# Sheet1.net
KiCad netlist of a schematic drawn in Altium Designer
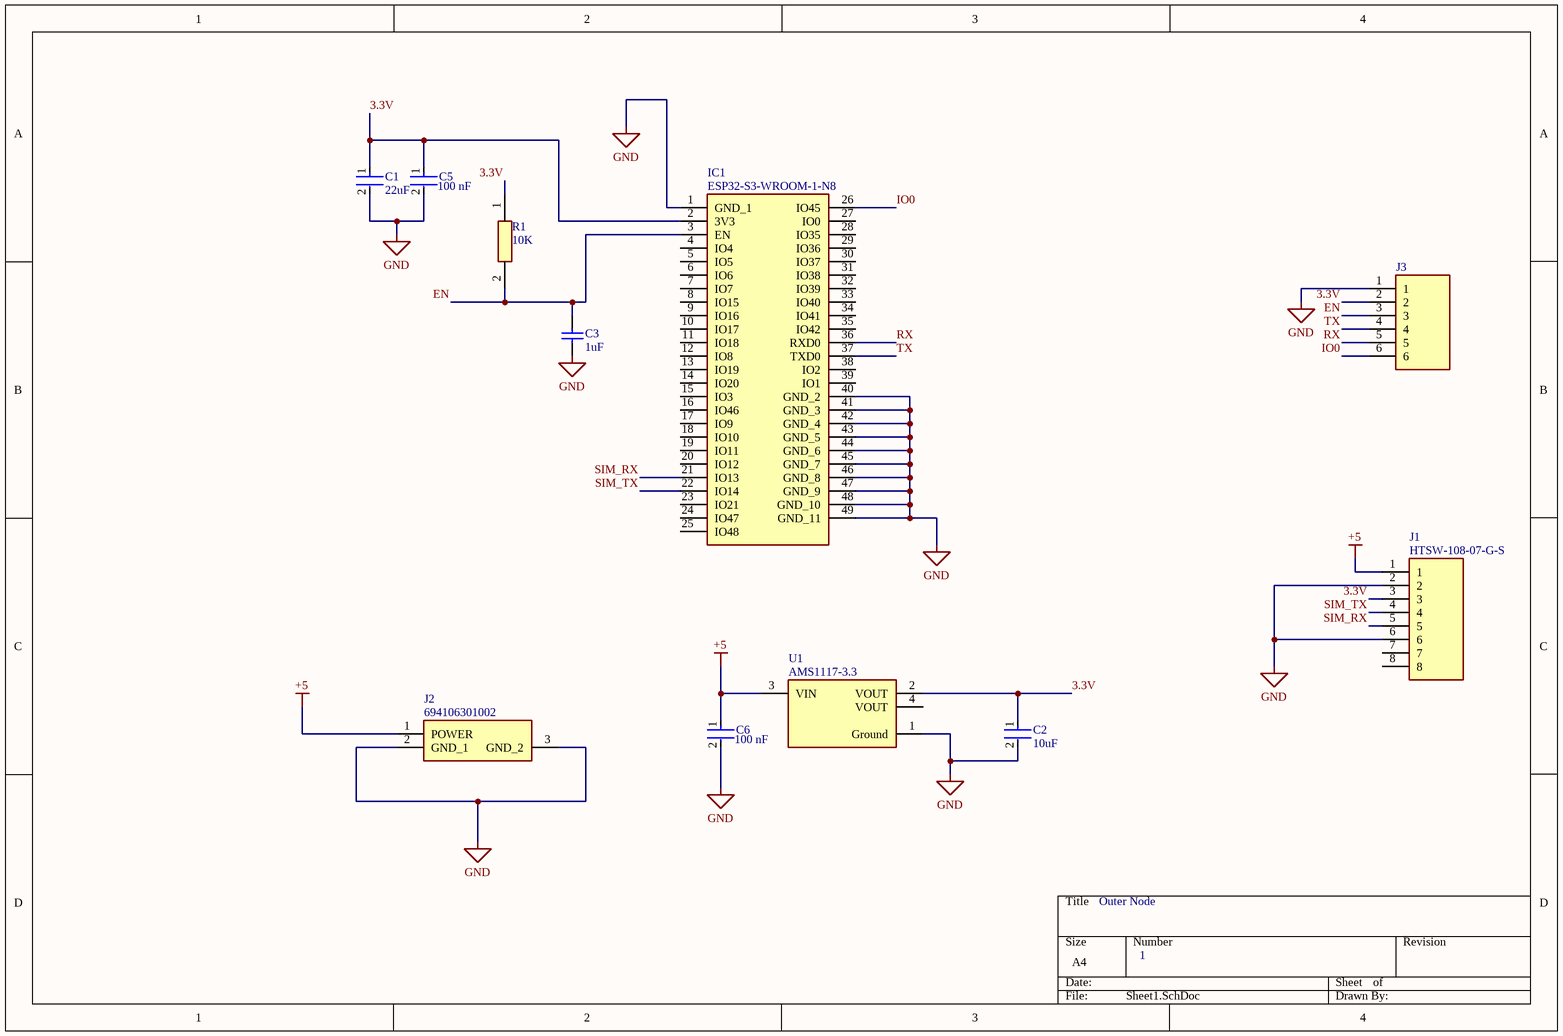
[diagram p0: Sheet1.SchDoc]

(export (version "E")
  (design (tool "Eeschema 10.0.6"))
  (components
    (comp (ref "C1")
      (value "22uF")
      (footprint "FP-CL21-IPC_C")
      (description "CL21 Series 0805 22uF 16V ±20% Tolerance X5R Multilayer Ceramic Chip Capacitor")
      (fields (field (name "TOLERANCE") "20%"))
      (libsource (lib "Altium Content Vault") (part "b4654b650e69147ec39a6b967a45e02"))
    )
    (comp (ref "C2")
      (value "10uF")
      (footprint "FP-CL21-IPC_B")
      (description "CL21 Series 0805 10uF 16V ±10% Tolerance X5R Multilayer Ceramic Chip Capacitor")
      (fields (field (name "VOLTAGE") "16V") (field (name "TOLERANCE") "10%"))
      (libsource (lib "Altium Content Vault") (part "b4654b650e69147ec39a6b967a45e02"))
    )
    (comp (ref "C3")
      (value "1uF")
      (footprint "CAPC2013X140X50LL20T25")
      (fields
        (field (name "PART NUMBER") "0805ZC105KAZ2A")
        (field (name "MANUFACTURER") "AVX Interconnect / Elco")
      )
      (libsource (lib "Altium Content Vault") (part "CAP"))
    )
    (comp (ref "C5")
      (value "CC0805KRX7R7BB104")
      (footprint "FP-CC0805-0_85-MFG")
      (description "CAP CER 0.1UF 16V X7R 0805")
      (fields
        (field (name "MANUFACTURER") "Yageo")
        (field (name "OCTOPART") "https://octopart.com/cc0805krx7r7bb104-yageo-39467769")
        (field (name "CAPACITANCE") "100 nF")
      )
      (libsource (lib "Altium Content Vault") (part "11868f565c42a9108669ba33697ecf6"))
    )
    (comp (ref "C6")
      (value "CC0805KRX7R7BB104")
      (footprint "FP-CC0805-0_85-MFG")
      (description "CAP CER 0.1UF 16V X7R 0805")
      (fields
        (field (name "MANUFACTURER") "Yageo")
        (field (name "OCTOPART") "https://octopart.com/cc0805krx7r7bb104-yageo-39467769")
        (field (name "CAPACITANCE") "100 nF")
      )
      (libsource (lib "Altium Content Vault") (part "11868f565c42a9108669ba33697ecf6"))
    )
    (comp (ref "IC1")
      (value "ESP32-S3-WROOM-1-N8")
      (footprint "SamacSys:ESP32S3WROOM1N8R2")
      (description "Integrated Circuit")
      (fields (field (name "MOUSER PART NUMBER") "356-ESP32-S3WROOM1N8"))
      (libsource (lib "*") (part "ESP32-S3-WROOM-1-N8"))
    )
    (comp (ref "J1")
      (value "HTSW-108-07-G-S")
      (footprint "SamacSys:HDRV8W64P0X254_1X8_2032X248X838P")
      (description "Connector")
      (fields (field (name "MOUSER PART NUMBER") "200-HTSW10807GS"))
      (libsource (lib "*") (part "HTSW-108-07-G-S"))
    )
    (comp (ref "J2")
      (value "694106301002")
      (footprint "SamacSys:694106301002_1")
      (description "Connector")
      (fields (field (name "MOUSER PART NUMBER") "710-694106301002"))
      (libsource (lib "*") (part "694106301002"))
    )
    (comp (ref "J3")
      (value "22-28-4060")
      (footprint "SamacSys:HDRV6W66P0X254_1X6_1524X249X838P")
      (description "Connector")
      (fields (field (name "MOUSER PART NUMBER") "538-22-28-4060"))
      (libsource (lib "*") (part "22-28-4060"))
    )
    (comp (ref "R1")
      (value "10K")
      (footprint "SamacSys:RESC2012X60N")
      (description "Resistor")
      (fields
        (field (name "MANUFACTURER_PART_NUMBER") "CMP0805AFX-1002ELF")
        (field (name "MOUSER PART NUMBER") "652-CMP0805AFX-1002L")
      )
      (libsource (lib "*") (part "CMP0805AFX-1002ELF"))
    )
    (comp (ref "U1")
      (value "AMS1117-3.3")
      (footprint "FP-AMS1117-IPC_C")
      (description "LDO Voltage Regulators 1A, 3.3V")
      (fields
        (field (name "OCTOPART") "https://octopart.com/ams1117-3.3-advanced+monolithic+systems-25899300")
        (field (name "MANUFACTURER") "Advanced Monolithic Systems")
      )
      (libsource (lib "Altium Content Vault") (part "8bdbb5f8e77002000e30dd2845d0354"))
    )
  )
  (nets
    (net (code "1") (name "+5") (class "Default")
      (node (ref "C6") (pin "1") (pinfunction "1_1") (pintype "passive"))
      (node (ref "J1") (pin "1") (pinfunction "1_1") (pintype "passive"))
      (node (ref "J2") (pin "1") (pinfunction "POWER_1") (pintype "passive"))
      (node (ref "U1") (pin "3") (pinfunction "VIN_3") (pintype "power_in"))
    )
    (net (code "2") (name "/3.3V") (class "Default")
      (node (ref "C1") (pin "1") (pinfunction "1_1") (pintype "passive"))
      (node (ref "C2") (pin "1") (pinfunction "1_1") (pintype "passive"))
      (node (ref "C5") (pin "1") (pinfunction "1_1") (pintype "passive"))
      (node (ref "IC1") (pin "2") (pinfunction "3V3_2") (pintype "passive"))
      (node (ref "J1") (pin "3") (pinfunction "3_3") (pintype "passive"))
      (node (ref "J3") (pin "2") (pinfunction "2_2") (pintype "passive"))
      (node (ref "R1") (pin "1") (pinfunction "1_1") (pintype "passive"))
      (node (ref "U1") (pin "2") (pinfunction "VOUT_2") (pintype "passive"))
    )
    (net (code "3") (name "/EN") (class "Default")
      (node (ref "C3") (pin "2") (pinfunction "2_2") (pintype "passive"))
      (node (ref "IC1") (pin "3") (pinfunction "EN_3") (pintype "passive"))
      (node (ref "J3") (pin "3") (pinfunction "3_3") (pintype "passive"))
      (node (ref "R1") (pin "2") (pinfunction "2_2") (pintype "passive"))
    )
    (net (code "4") (name "/IO0") (class "Default")
      (node (ref "IC1") (pin "26") (pinfunction "IO45_26") (pintype "passive"))
      (node (ref "J3") (pin "6") (pinfunction "6_6") (pintype "passive"))
    )
    (net (code "5") (name "/RX") (class "Default")
      (node (ref "IC1") (pin "36") (pinfunction "RXD0_36") (pintype "passive"))
      (node (ref "J3") (pin "5") (pinfunction "5_5") (pintype "passive"))
    )
    (net (code "6") (name "/SIM_RX") (class "Default")
      (node (ref "IC1") (pin "21") (pinfunction "IO13_21") (pintype "passive"))
      (node (ref "J1") (pin "5") (pinfunction "5_5") (pintype "passive"))
    )
    (net (code "7") (name "/SIM_TX") (class "Default")
      (node (ref "IC1") (pin "22") (pinfunction "IO14_22") (pintype "passive"))
      (node (ref "J1") (pin "4") (pinfunction "4_4") (pintype "passive"))
    )
    (net (code "8") (name "/TX") (class "Default")
      (node (ref "IC1") (pin "37") (pinfunction "TXD0_37") (pintype "passive"))
      (node (ref "J3") (pin "4") (pinfunction "4_4") (pintype "passive"))
    )
    (net (code "9") (name "GND") (class "Default")
      (node (ref "C1") (pin "2") (pinfunction "2_2") (pintype "passive"))
      (node (ref "C2") (pin "2") (pinfunction "2_2") (pintype "passive"))
      (node (ref "C3") (pin "1") (pinfunction "1_1") (pintype "passive"))
      (node (ref "C5") (pin "2") (pinfunction "2_2") (pintype "passive"))
      (node (ref "C6") (pin "2") (pinfunction "2_2") (pintype "passive"))
      (node (ref "IC1") (pin "1") (pinfunction "GND_1_1") (pintype "passive"))
      (node (ref "IC1") (pin "40") (pinfunction "GND_2_40") (pintype "passive"))
      (node (ref "IC1") (pin "41") (pinfunction "GND_3_41") (pintype "passive"))
      (node (ref "IC1") (pin "42") (pinfunction "GND_4_42") (pintype "passive"))
      (node (ref "IC1") (pin "43") (pinfunction "GND_5_43") (pintype "passive"))
      (node (ref "IC1") (pin "44") (pinfunction "GND_6_44") (pintype "passive"))
      (node (ref "IC1") (pin "45") (pinfunction "GND_7_45") (pintype "passive"))
      (node (ref "IC1") (pin "46") (pinfunction "GND_8_46") (pintype "passive"))
      (node (ref "IC1") (pin "47") (pinfunction "GND_9_47") (pintype "passive"))
      (node (ref "IC1") (pin "48") (pinfunction "GND_10_48") (pintype "passive"))
      (node (ref "IC1") (pin "49") (pinfunction "GND_11_49") (pintype "passive"))
      (node (ref "J1") (pin "2") (pinfunction "2_2") (pintype "passive"))
      (node (ref "J1") (pin "6") (pinfunction "6_6") (pintype "passive"))
      (node (ref "J2") (pin "2") (pinfunction "GND_1_2") (pintype "passive"))
      (node (ref "J2") (pin "3") (pinfunction "GND_2_3") (pintype "passive"))
      (node (ref "J3") (pin "1") (pinfunction "1_1") (pintype "passive"))
      (node (ref "U1") (pin "1") (pinfunction "Ground_1") (pintype "power_in"))
    )
    (net (code "10") (name "unconnected-(IC1-IO0-Pad27)") (class "Default")
      (node (ref "IC1") (pin "27") (pinfunction "IO0_27") (pintype "passive"))
    )
    (net (code "11") (name "unconnected-(IC1-IO1-Pad39)") (class "Default")
      (node (ref "IC1") (pin "39") (pinfunction "IO1_39") (pintype "passive"))
    )
    (net (code "12") (name "unconnected-(IC1-IO2-Pad38)") (class "Default")
      (node (ref "IC1") (pin "38") (pinfunction "IO2_38") (pintype "passive"))
    )
    (net (code "13") (name "unconnected-(IC1-IO3-Pad15)") (class "Default")
      (node (ref "IC1") (pin "15") (pinfunction "IO3_15") (pintype "passive"))
    )
    (net (code "14") (name "unconnected-(IC1-IO4-Pad4)") (class "Default")
      (node (ref "IC1") (pin "4") (pinfunction "IO4_4") (pintype "passive"))
    )
    (net (code "15") (name "unconnected-(IC1-IO5-Pad5)") (class "Default")
      (node (ref "IC1") (pin "5") (pinfunction "IO5_5") (pintype "passive"))
    )
    (net (code "16") (name "unconnected-(IC1-IO6-Pad6)") (class "Default")
      (node (ref "IC1") (pin "6") (pinfunction "IO6_6") (pintype "passive"))
    )
    (net (code "17") (name "unconnected-(IC1-IO7-Pad7)") (class "Default")
      (node (ref "IC1") (pin "7") (pinfunction "IO7_7") (pintype "passive"))
    )
    (net (code "18") (name "unconnected-(IC1-IO8-Pad12)") (class "Default")
      (node (ref "IC1") (pin "12") (pinfunction "IO8_12") (pintype "passive"))
    )
    (net (code "19") (name "unconnected-(IC1-IO9-Pad17)") (class "Default")
      (node (ref "IC1") (pin "17") (pinfunction "IO9_17") (pintype "passive"))
    )
    (net (code "20") (name "unconnected-(IC1-IO10-Pad18)") (class "Default")
      (node (ref "IC1") (pin "18") (pinfunction "IO10_18") (pintype "passive"))
    )
    (net (code "21") (name "unconnected-(IC1-IO11-Pad19)") (class "Default")
      (node (ref "IC1") (pin "19") (pinfunction "IO11_19") (pintype "passive"))
    )
    (net (code "22") (name "unconnected-(IC1-IO12-Pad20)") (class "Default")
      (node (ref "IC1") (pin "20") (pinfunction "IO12_20") (pintype "passive"))
    )
    (net (code "23") (name "unconnected-(IC1-IO15-Pad8)") (class "Default")
      (node (ref "IC1") (pin "8") (pinfunction "IO15_8") (pintype "passive"))
    )
    (net (code "24") (name "unconnected-(IC1-IO16-Pad9)") (class "Default")
      (node (ref "IC1") (pin "9") (pinfunction "IO16_9") (pintype "passive"))
    )
    (net (code "25") (name "unconnected-(IC1-IO17-Pad10)") (class "Default")
      (node (ref "IC1") (pin "10") (pinfunction "IO17_10") (pintype "passive"))
    )
    (net (code "26") (name "unconnected-(IC1-IO18-Pad11)") (class "Default")
      (node (ref "IC1") (pin "11") (pinfunction "IO18_11") (pintype "passive"))
    )
    (net (code "27") (name "unconnected-(IC1-IO19-Pad13)") (class "Default")
      (node (ref "IC1") (pin "13") (pinfunction "IO19_13") (pintype "passive"))
    )
    (net (code "28") (name "unconnected-(IC1-IO20-Pad14)") (class "Default")
      (node (ref "IC1") (pin "14") (pinfunction "IO20_14") (pintype "passive"))
    )
    (net (code "29") (name "unconnected-(IC1-IO21-Pad23)") (class "Default")
      (node (ref "IC1") (pin "23") (pinfunction "IO21_23") (pintype "passive"))
    )
    (net (code "30") (name "unconnected-(IC1-IO35-Pad28)") (class "Default")
      (node (ref "IC1") (pin "28") (pinfunction "IO35_28") (pintype "passive"))
    )
    (net (code "31") (name "unconnected-(IC1-IO36-Pad29)") (class "Default")
      (node (ref "IC1") (pin "29") (pinfunction "IO36_29") (pintype "passive"))
    )
    (net (code "32") (name "unconnected-(IC1-IO37-Pad30)") (class "Default")
      (node (ref "IC1") (pin "30") (pinfunction "IO37_30") (pintype "passive"))
    )
    (net (code "33") (name "unconnected-(IC1-IO38-Pad31)") (class "Default")
      (node (ref "IC1") (pin "31") (pinfunction "IO38_31") (pintype "passive"))
    )
    (net (code "34") (name "unconnected-(IC1-IO39-Pad32)") (class "Default")
      (node (ref "IC1") (pin "32") (pinfunction "IO39_32") (pintype "passive"))
    )
    (net (code "35") (name "unconnected-(IC1-IO40-Pad33)") (class "Default")
      (node (ref "IC1") (pin "33") (pinfunction "IO40_33") (pintype "passive"))
    )
    (net (code "36") (name "unconnected-(IC1-IO41-Pad34)") (class "Default")
      (node (ref "IC1") (pin "34") (pinfunction "IO41_34") (pintype "passive"))
    )
    (net (code "37") (name "unconnected-(IC1-IO42-Pad35)") (class "Default")
      (node (ref "IC1") (pin "35") (pinfunction "IO42_35") (pintype "passive"))
    )
    (net (code "38") (name "unconnected-(IC1-IO46-Pad16)") (class "Default")
      (node (ref "IC1") (pin "16") (pinfunction "IO46_16") (pintype "passive"))
    )
    (net (code "39") (name "unconnected-(IC1-IO47-Pad24)") (class "Default")
      (node (ref "IC1") (pin "24") (pinfunction "IO47_24") (pintype "passive"))
    )
    (net (code "40") (name "unconnected-(IC1-IO48-Pad25)") (class "Default")
      (node (ref "IC1") (pin "25") (pinfunction "IO48_25") (pintype "passive"))
    )
    (net (code "41") (name "unconnected-(J1-Pad7)") (class "Default")
      (node (ref "J1") (pin "7") (pinfunction "7_7") (pintype "passive"))
    )
    (net (code "42") (name "unconnected-(J1-Pad8)") (class "Default")
      (node (ref "J1") (pin "8") (pinfunction "8_8") (pintype "passive"))
    )
    (net (code "43") (name "unconnected-(U1-VOUT-Pad4)") (class "Default")
      (node (ref "U1") (pin "4") (pinfunction "VOUT_4") (pintype "passive"))
    )
  )
)
